# Motor_main.net
KiCad netlist of a schematic drawn in EasyEDA Pro
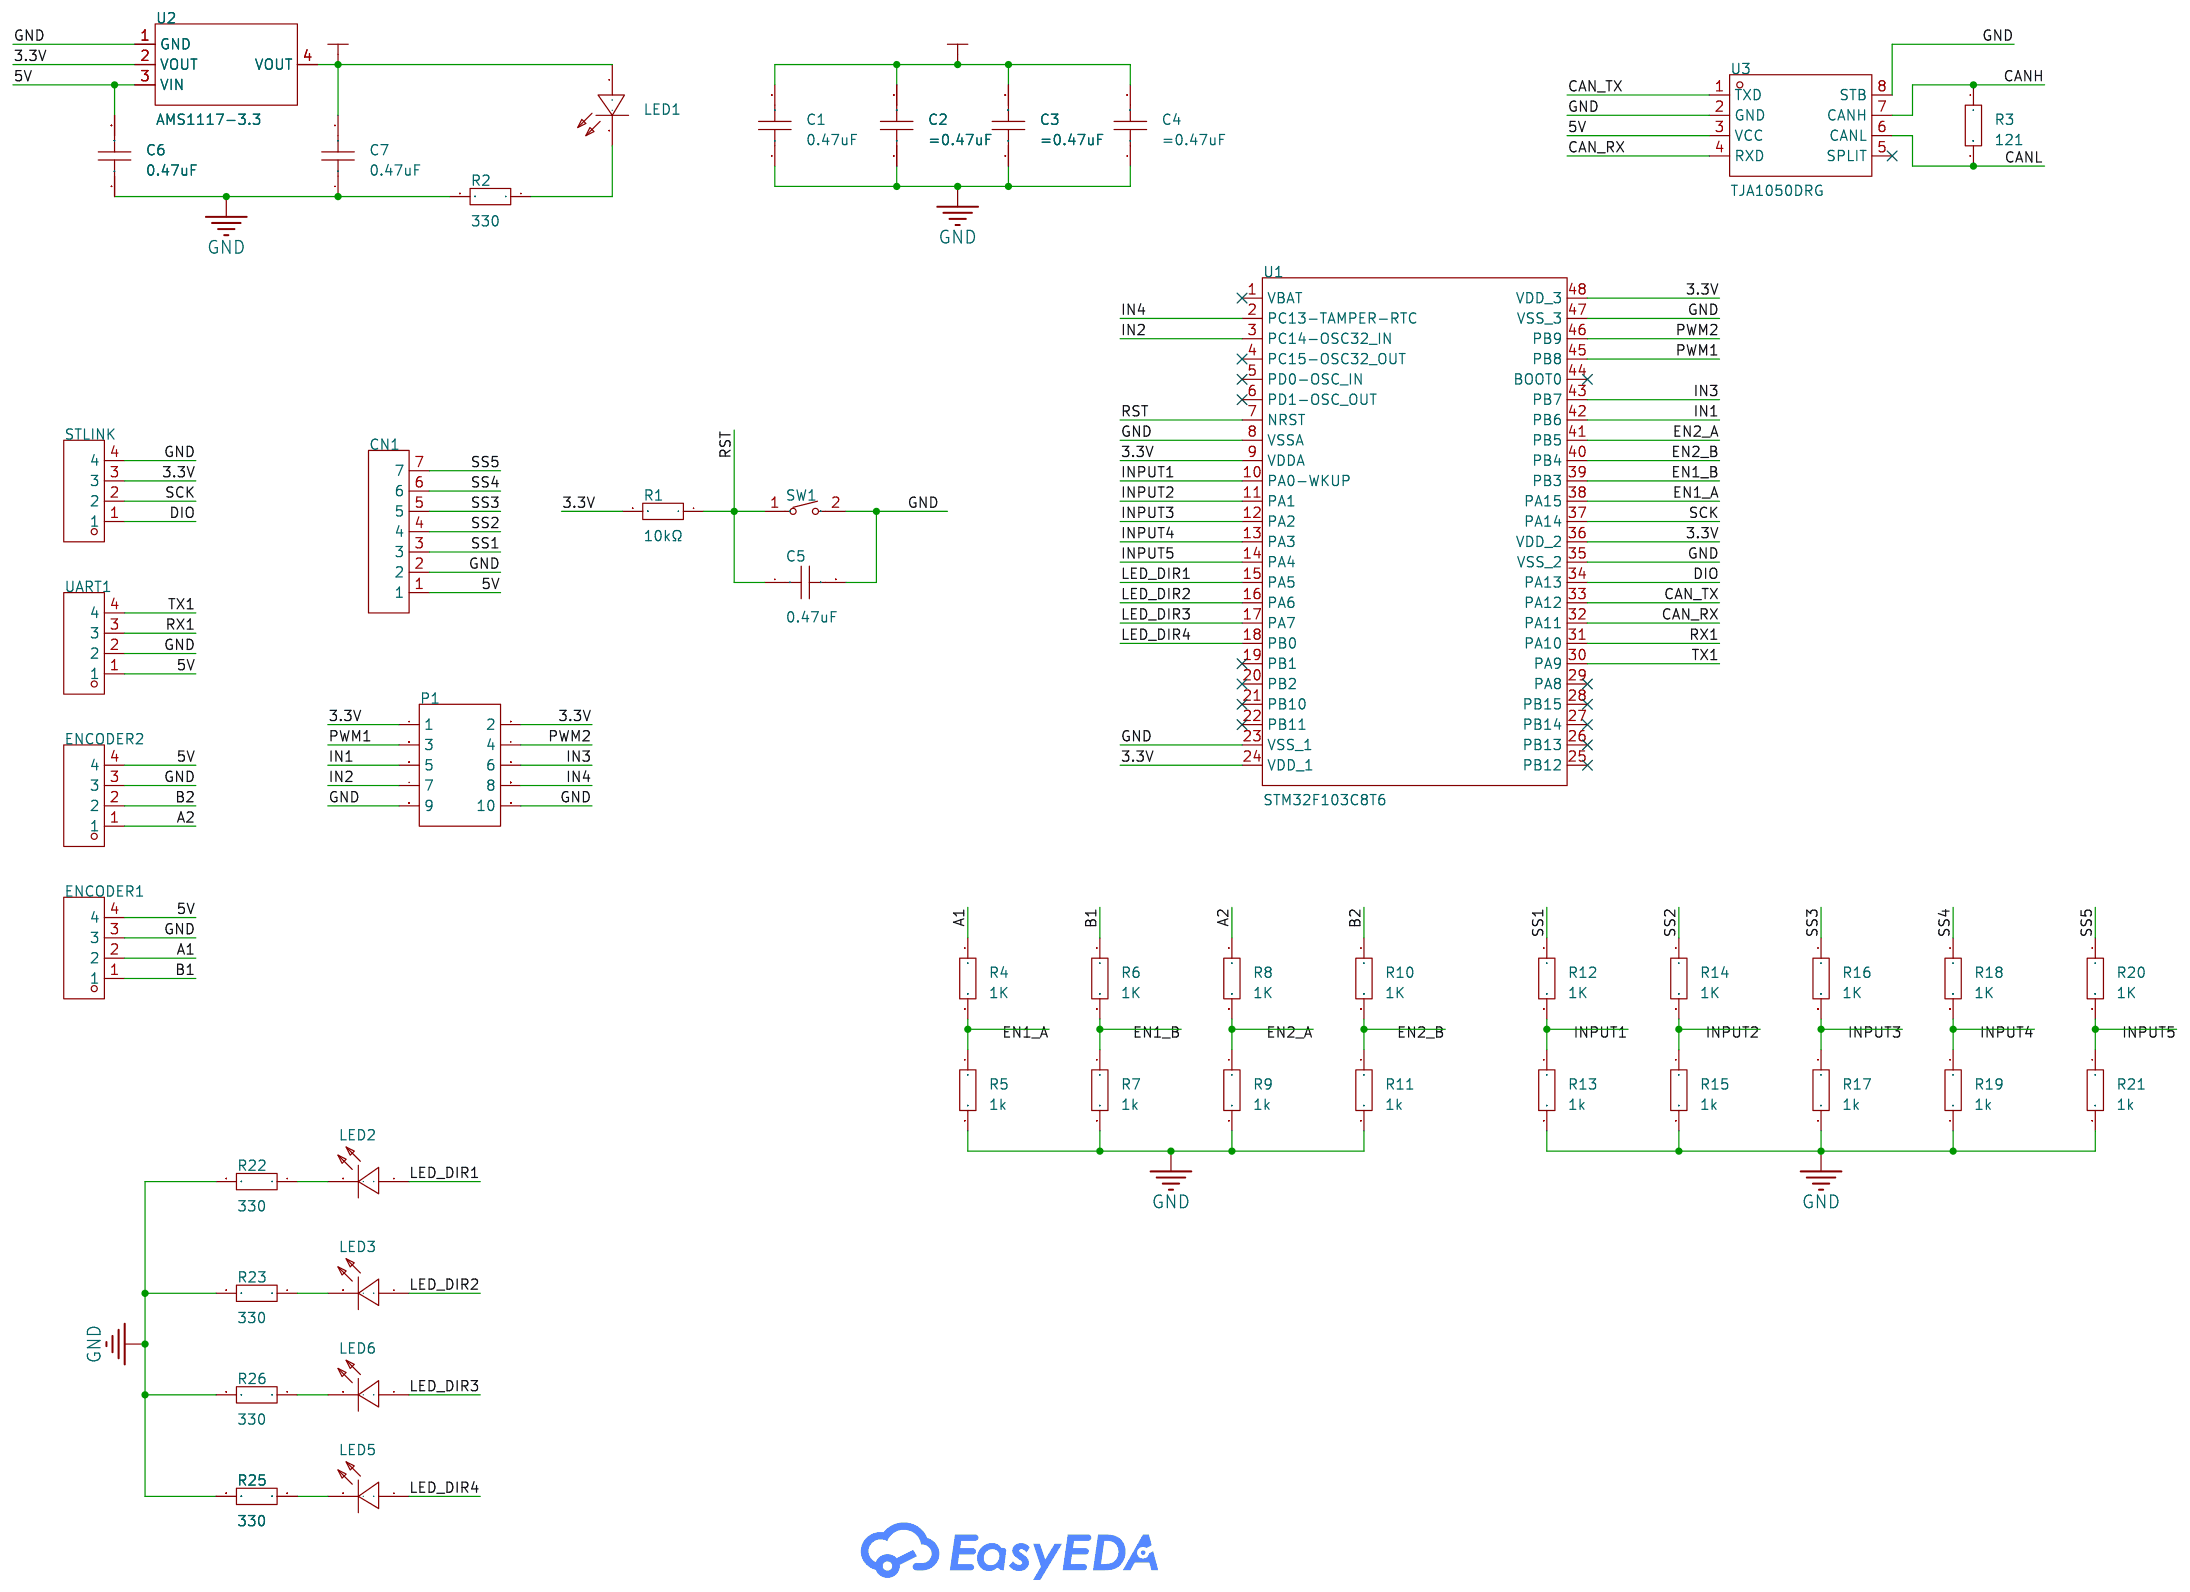
[diagram p0: schematic sheet]

(export (version "E")
  (design (tool "Eeschema 10.0.6"))
  (components
    (comp (ref "C1")
      (value "0.47uF")
      (footprint "easyedapro:C0805")
      (description "Capacitance:100nF Tolerance:±10% Tolerance:±10% Voltage Rating:50V Temperature Coefficient:X7R")
      (fields
        (field (name "Manufacturer Part") "CC0805KRX7R9BB104")
        (field (name "Manufacturer") "YAGEO(国巨)")
      )
      (libsource (lib "easyedapro") (part "CC0805KRX7R9BB104"))
    )
    (comp (ref "C2")
      (value "100nF")
      (footprint "easyedapro:C0805")
      (description "Capacitance:100nF Tolerance:±10% Tolerance:±10% Voltage Rating:50V Temperature Coefficient:X7R")
      (fields
        (field (name "Manufacturer Part") "CC0805KRX7R9BB104")
        (field (name "Manufacturer") "YAGEO(国巨)")
      )
      (libsource (lib "easyedapro") (part "CC0805KRX7R9BB104"))
    )
    (comp (ref "C3")
      (value "100nF")
      (footprint "easyedapro:C0805")
      (description "Capacitance:100nF Tolerance:±10% Tolerance:±10% Voltage Rating:50V Temperature Coefficient:X7R")
      (fields
        (field (name "Manufacturer Part") "CC0805KRX7R9BB104")
        (field (name "Manufacturer") "YAGEO(国巨)")
      )
      (libsource (lib "easyedapro") (part "CC0805KRX7R9BB104"))
    )
    (comp (ref "C4")
      (value "100nF")
      (footprint "easyedapro:C0805")
      (description "Capacitance:100nF Tolerance:±10% Tolerance:±10% Voltage Rating:50V Temperature Coefficient:X7R")
      (fields
        (field (name "Manufacturer Part") "CC0805KRX7R9BB104")
        (field (name "Manufacturer") "YAGEO(国巨)")
      )
      (libsource (lib "easyedapro") (part "CC0805KRX7R9BB104"))
    )
    (comp (ref "C5")
      (value "0.47uF")
      (footprint "easyedapro:C0805")
      (description "Capacitance:100nF Tolerance:±10% Tolerance:±10% Voltage Rating:50V Temperature Coefficient:X7R")
      (fields
        (field (name "Manufacturer Part") "CC0805KRX7R9BB104")
        (field (name "Manufacturer") "YAGEO(国巨)")
      )
      (libsource (lib "easyedapro") (part "CC0805KRX7R9BB104"))
    )
    (comp (ref "C6")
      (value "0.47uF")
      (footprint "easyedapro:C0805")
      (description "Capacitance:100nF Tolerance:±10% Tolerance:±10% Voltage Rating:50V Temperature Coefficient:X7R")
      (fields
        (field (name "Manufacturer Part") "CC0805KRX7R9BB104")
        (field (name "Manufacturer") "YAGEO(国巨)")
      )
      (libsource (lib "easyedapro") (part "CC0805KRX7R9BB104"))
    )
    (comp (ref "C7")
      (value "0.47uF")
      (footprint "easyedapro:C0805")
      (description "Capacitance:100nF Tolerance:±10% Tolerance:±10% Voltage Rating:50V Temperature Coefficient:X7R")
      (fields
        (field (name "Manufacturer Part") "CC0805KRX7R9BB104")
        (field (name "Manufacturer") "YAGEO(国巨)")
      )
      (libsource (lib "easyedapro") (part "CC0805KRX7R9BB104"))
    )
    (comp (ref "CN1")
      (value "WAFER-XH254Z-7AL")
      (footprint "easyedapro:CONN-TH_7P-P2.50_WAFER-XH254Z-7A")
      (fields (field (name "Manufacturer") "HANBO(汉博)"))
      (libsource (lib "easyedapro") (part "WAFER-XH254Z-7AL"))
    )
    (comp (ref "ENCODER1")
      (value "ZX-XH2.54-4PZZ")
      (footprint "easyedapro:CONN-TH_4P-P2.50_4PIN")
      (fields (field (name "Manufacturer") "Megastar(兆星)"))
      (libsource (lib "easyedapro") (part "ZX-XH2.54-4PZZ"))
    )
    (comp (ref "ENCODER2")
      (value "ZX-XH2.54-4PZZ")
      (footprint "easyedapro:CONN-TH_4P-P2.50_4PIN")
      (fields (field (name "Manufacturer") "Megastar(兆星)"))
      (libsource (lib "easyedapro") (part "ZX-XH2.54-4PZZ"))
    )
    (comp (ref "LED1")
      (value "YLED0805R")
      (footprint "easyedapro:LED0805-R-RD_RED")
      (fields (field (name "Manufacturer") "YONGYUTAI(永裕泰)"))
      (libsource (lib "easyedapro") (part "YLED0805R"))
    )
    (comp (ref "LED2")
      (value "YLED0805R")
      (footprint "easyedapro:LED0805-R-RD_RED")
      (fields (field (name "Manufacturer") "YONGYUTAI(永裕泰)"))
      (libsource (lib "easyedapro") (part "YLED0805R"))
    )
    (comp (ref "LED3")
      (value "YLED0805R")
      (footprint "easyedapro:LED0805-R-RD_RED")
      (fields (field (name "Manufacturer") "YONGYUTAI(永裕泰)"))
      (libsource (lib "easyedapro") (part "YLED0805R"))
    )
    (comp (ref "LED5")
      (value "YLED0805R")
      (footprint "easyedapro:LED0805-R-RD_RED")
      (fields (field (name "Manufacturer") "YONGYUTAI(永裕泰)"))
      (libsource (lib "easyedapro") (part "YLED0805R"))
    )
    (comp (ref "LED6")
      (value "YLED0805R")
      (footprint "easyedapro:LED0805-R-RD_RED")
      (fields (field (name "Manufacturer") "YONGYUTAI(永裕泰)"))
      (libsource (lib "easyedapro") (part "YLED0805R"))
    )
    (comp (ref "P1")
      (value "2.54-2*5P简牛")
      (footprint "easyedapro:IDC-TH_10P-P2.54_C5665")
      (fields (field (name "Manufacturer") "BOOMELE(博穆精密)"))
      (libsource (lib "easyedapro") (part "HDR-IDC-2.54-2X5P"))
    )
    (comp (ref "R1")
      (value "10kΩ")
      (footprint "easyedapro:R0805")
      (fields (field (name "Manufacturer Part") "RC0805FR-0710KL") (field (name "Manufacturer") "YAGEO(国巨)"))
      (libsource (lib "easyedapro") (part "RC0805FR-0710KL"))
    )
    (comp (ref "R2")
      (value "10kΩ")
      (footprint "easyedapro:R0805")
      (fields (field (name "Manufacturer Part") "RC0805FR-0710KL") (field (name "Manufacturer") "YAGEO(国巨)"))
      (libsource (lib "easyedapro") (part "RC0805FR-0710KL"))
    )
    (comp (ref "R3")
      (value "10kΩ")
      (footprint "easyedapro:R0805")
      (fields (field (name "Manufacturer Part") "RC0805FR-0710KL") (field (name "Manufacturer") "YAGEO(国巨)"))
      (libsource (lib "easyedapro") (part "RC0805FR-0710KL"))
    )
    (comp (ref "R4")
      (value "1K")
      (footprint "easyedapro:R0805")
      (fields (field (name "Manufacturer Part") "RC0805FR-0710KL") (field (name "Manufacturer") "YAGEO(国巨)"))
      (libsource (lib "easyedapro") (part "RC0805FR-0710KL"))
    )
    (comp (ref "R5")
      (value "1k")
      (footprint "easyedapro:R0805")
      (fields (field (name "Manufacturer Part") "RC0805FR-0710KL") (field (name "Manufacturer") "YAGEO(国巨)"))
      (libsource (lib "easyedapro") (part "RC0805FR-0710KL"))
    )
    (comp (ref "R6")
      (value "1K")
      (footprint "easyedapro:R0805")
      (fields (field (name "Manufacturer Part") "RC0805FR-0710KL") (field (name "Manufacturer") "YAGEO(国巨)"))
      (libsource (lib "easyedapro") (part "RC0805FR-0710KL"))
    )
    (comp (ref "R7")
      (value "1k")
      (footprint "easyedapro:R0805")
      (fields (field (name "Manufacturer Part") "RC0805FR-0710KL") (field (name "Manufacturer") "YAGEO(国巨)"))
      (libsource (lib "easyedapro") (part "RC0805FR-0710KL"))
    )
    (comp (ref "R8")
      (value "1K")
      (footprint "easyedapro:R0805")
      (fields (field (name "Manufacturer Part") "RC0805FR-0710KL") (field (name "Manufacturer") "YAGEO(国巨)"))
      (libsource (lib "easyedapro") (part "RC0805FR-0710KL"))
    )
    (comp (ref "R9")
      (value "1k")
      (footprint "easyedapro:R0805")
      (fields (field (name "Manufacturer Part") "RC0805FR-0710KL") (field (name "Manufacturer") "YAGEO(国巨)"))
      (libsource (lib "easyedapro") (part "RC0805FR-0710KL"))
    )
    (comp (ref "R10")
      (value "1K")
      (footprint "easyedapro:R0805")
      (fields (field (name "Manufacturer Part") "RC0805FR-0710KL") (field (name "Manufacturer") "YAGEO(国巨)"))
      (libsource (lib "easyedapro") (part "RC0805FR-0710KL"))
    )
    (comp (ref "R11")
      (value "1k")
      (footprint "easyedapro:R0805")
      (fields (field (name "Manufacturer Part") "RC0805FR-0710KL") (field (name "Manufacturer") "YAGEO(国巨)"))
      (libsource (lib "easyedapro") (part "RC0805FR-0710KL"))
    )
    (comp (ref "R12")
      (value "1K")
      (footprint "easyedapro:R0805")
      (fields (field (name "Manufacturer Part") "RC0805FR-0710KL") (field (name "Manufacturer") "YAGEO(国巨)"))
      (libsource (lib "easyedapro") (part "RC0805FR-0710KL"))
    )
    (comp (ref "R13")
      (value "1k")
      (footprint "easyedapro:R0805")
      (fields (field (name "Manufacturer Part") "RC0805FR-0710KL") (field (name "Manufacturer") "YAGEO(国巨)"))
      (libsource (lib "easyedapro") (part "RC0805FR-0710KL"))
    )
    (comp (ref "R14")
      (value "1K")
      (footprint "easyedapro:R0805")
      (fields (field (name "Manufacturer Part") "RC0805FR-0710KL") (field (name "Manufacturer") "YAGEO(国巨)"))
      (libsource (lib "easyedapro") (part "RC0805FR-0710KL"))
    )
    (comp (ref "R15")
      (value "1k")
      (footprint "easyedapro:R0805")
      (fields (field (name "Manufacturer Part") "RC0805FR-0710KL") (field (name "Manufacturer") "YAGEO(国巨)"))
      (libsource (lib "easyedapro") (part "RC0805FR-0710KL"))
    )
    (comp (ref "R16")
      (value "1K")
      (footprint "easyedapro:R0805")
      (fields (field (name "Manufacturer Part") "RC0805FR-0710KL") (field (name "Manufacturer") "YAGEO(国巨)"))
      (libsource (lib "easyedapro") (part "RC0805FR-0710KL"))
    )
    (comp (ref "R17")
      (value "1k")
      (footprint "easyedapro:R0805")
      (fields (field (name "Manufacturer Part") "RC0805FR-0710KL") (field (name "Manufacturer") "YAGEO(国巨)"))
      (libsource (lib "easyedapro") (part "RC0805FR-0710KL"))
    )
    (comp (ref "R18")
      (value "1K")
      (footprint "easyedapro:R0805")
      (fields (field (name "Manufacturer Part") "RC0805FR-0710KL") (field (name "Manufacturer") "YAGEO(国巨)"))
      (libsource (lib "easyedapro") (part "RC0805FR-0710KL"))
    )
    (comp (ref "R19")
      (value "1k")
      (footprint "easyedapro:R0805")
      (fields (field (name "Manufacturer Part") "RC0805FR-0710KL") (field (name "Manufacturer") "YAGEO(国巨)"))
      (libsource (lib "easyedapro") (part "RC0805FR-0710KL"))
    )
    (comp (ref "R20")
      (value "1K")
      (footprint "easyedapro:R0805")
      (fields (field (name "Manufacturer Part") "RC0805FR-0710KL") (field (name "Manufacturer") "YAGEO(国巨)"))
      (libsource (lib "easyedapro") (part "RC0805FR-0710KL"))
    )
    (comp (ref "R21")
      (value "1k")
      (footprint "easyedapro:R0805")
      (fields (field (name "Manufacturer Part") "RC0805FR-0710KL") (field (name "Manufacturer") "YAGEO(国巨)"))
      (libsource (lib "easyedapro") (part "RC0805FR-0710KL"))
    )
    (comp (ref "R22")
      (value "10kΩ")
      (footprint "easyedapro:R0805")
      (fields (field (name "Manufacturer Part") "RC0805FR-0710KL") (field (name "Manufacturer") "YAGEO(国巨)"))
      (libsource (lib "easyedapro") (part "RC0805FR-0710KL"))
    )
    (comp (ref "R23")
      (value "10kΩ")
      (footprint "easyedapro:R0805")
      (fields (field (name "Manufacturer Part") "RC0805FR-0710KL") (field (name "Manufacturer") "YAGEO(国巨)"))
      (libsource (lib "easyedapro") (part "RC0805FR-0710KL"))
    )
    (comp (ref "R25")
      (value "10kΩ")
      (footprint "easyedapro:R0805")
      (fields (field (name "Manufacturer Part") "RC0805FR-0710KL") (field (name "Manufacturer") "YAGEO(国巨)"))
      (libsource (lib "easyedapro") (part "RC0805FR-0710KL"))
    )
    (comp (ref "R26")
      (value "10kΩ")
      (footprint "easyedapro:R0805")
      (fields (field (name "Manufacturer Part") "RC0805FR-0710KL") (field (name "Manufacturer") "YAGEO(国巨)"))
      (libsource (lib "easyedapro") (part "RC0805FR-0710KL"))
    )
    (comp (ref "STLINK")
      (value "ZX-XH2.54-4PZZ")
      (footprint "easyedapro:CONN-TH_4P-P2.50_4PIN")
      (fields (field (name "Manufacturer") "Megastar(兆星)"))
      (libsource (lib "easyedapro") (part "ZX-XH2.54-4PZZ"))
    )
    (comp (ref "SW1")
      (value "GT-TC060A-H025-L1S")
      (footprint "easyedapro:SW-SMD_L6.1-W3.5-LS8.0")
      (fields (field (name "Manufacturer") "G-Switch(品赞)"))
      (libsource (lib "easyedapro") (part "GT-TC060A-H025-L1S"))
    )
    (comp (ref "U1")
      (value "STM32F103C8T6")
      (footprint "easyedapro:LQFP-48_L7.0-W7.0-P0.50-LS9.0-BL")
      (fields (field (name "Manufacturer") "ST(意法半导体)"))
      (libsource (lib "easyedapro") (part "STM32F103C8T6"))
    )
    (comp (ref "U2")
      (value "AMS1117-3.3")
      (footprint "easyedapro:SOT-223-3_L6.5-W3.4-P2.30-LS7.0-BR")
      (fields (field (name "Manufacturer") "AMS"))
      (libsource (lib "easyedapro") (part "AMS1117-3.3"))
    )
    (comp (ref "U3")
      (value "TJA1050DRG")
      (footprint "easyedapro:SOP-8_L4.9-W3.9-P1.27-LS6.0-BL")
      (fields (field (name "Manufacturer") "HGC(深圳汉芯)"))
      (libsource (lib "easyedapro") (part "TJA1050DRG"))
    )
    (comp (ref "UART1")
      (value "ZX-XH2.54-4PZZ")
      (footprint "easyedapro:CONN-TH_4P-P2.50_4PIN")
      (fields (field (name "Manufacturer") "Megastar(兆星)"))
      (libsource (lib "easyedapro") (part "ZX-XH2.54-4PZZ"))
    )
  )
  (nets
    (net (code "1") (name "/5V") (class "Default")
      (node (ref "C6") (pin "2") (pinfunction "2_2") (pintype "unspecified"))
      (node (ref "CN1") (pin "1") (pinfunction "1_1") (pintype "unspecified"))
      (node (ref "ENCODER1") (pin "4") (pinfunction "4_4") (pintype "unspecified"))
      (node (ref "ENCODER2") (pin "4") (pinfunction "4_4") (pintype "unspecified"))
      (node (ref "U2") (pin "3") (pinfunction "VIN_3") (pintype "unspecified"))
      (node (ref "U3") (pin "3") (pinfunction "VCC_3") (pintype "unspecified"))
      (node (ref "UART1") (pin "1") (pinfunction "1_1") (pintype "unspecified"))
    )
    (net (code "2") (name "/A1") (class "Default")
      (node (ref "ENCODER1") (pin "2") (pinfunction "2_2") (pintype "unspecified"))
      (node (ref "R4") (pin "1") (pinfunction "1_1") (pintype "input"))
    )
    (net (code "3") (name "/A2") (class "Default")
      (node (ref "ENCODER2") (pin "1") (pinfunction "1_1") (pintype "unspecified"))
      (node (ref "R8") (pin "1") (pinfunction "1_1") (pintype "input"))
    )
    (net (code "4") (name "/B1") (class "Default")
      (node (ref "ENCODER1") (pin "1") (pinfunction "1_1") (pintype "unspecified"))
      (node (ref "R6") (pin "1") (pinfunction "1_1") (pintype "input"))
    )
    (net (code "5") (name "/B2") (class "Default")
      (node (ref "ENCODER2") (pin "2") (pinfunction "2_2") (pintype "unspecified"))
      (node (ref "R10") (pin "1") (pinfunction "1_1") (pintype "input"))
    )
    (net (code "6") (name "/CANH") (class "Default")
      (node (ref "R3") (pin "1") (pinfunction "1_1") (pintype "input"))
      (node (ref "U3") (pin "7") (pinfunction "CANH_7") (pintype "unspecified"))
    )
    (net (code "7") (name "/CANL") (class "Default")
      (node (ref "R3") (pin "2") (pinfunction "2_2") (pintype "input"))
      (node (ref "U3") (pin "6") (pinfunction "CANL_6") (pintype "unspecified"))
    )
    (net (code "8") (name "/CAN_RX") (class "Default")
      (node (ref "U1") (pin "32") (pinfunction "PA11_32") (pintype "unspecified"))
      (node (ref "U3") (pin "4") (pinfunction "RXD_4") (pintype "unspecified"))
    )
    (net (code "9") (name "/CAN_TX") (class "Default")
      (node (ref "U1") (pin "33") (pinfunction "PA12_33") (pintype "unspecified"))
      (node (ref "U3") (pin "1") (pinfunction "TXD_1") (pintype "unspecified"))
    )
    (net (code "10") (name "/DIO") (class "Default")
      (node (ref "STLINK") (pin "1") (pinfunction "1_1") (pintype "unspecified"))
      (node (ref "U1") (pin "34") (pinfunction "PA13_34") (pintype "unspecified"))
    )
    (net (code "11") (name "/EN1_A") (class "Default")
      (node (ref "R4") (pin "2") (pinfunction "2_2") (pintype "input"))
      (node (ref "R5") (pin "1") (pinfunction "1_1") (pintype "input"))
      (node (ref "U1") (pin "38") (pinfunction "PA15_38") (pintype "unspecified"))
    )
    (net (code "12") (name "/EN1_B") (class "Default")
      (node (ref "R6") (pin "2") (pinfunction "2_2") (pintype "input"))
      (node (ref "R7") (pin "1") (pinfunction "1_1") (pintype "input"))
      (node (ref "U1") (pin "39") (pinfunction "PB3_39") (pintype "unspecified"))
    )
    (net (code "13") (name "/EN2_A") (class "Default")
      (node (ref "R8") (pin "2") (pinfunction "2_2") (pintype "input"))
      (node (ref "R9") (pin "1") (pinfunction "1_1") (pintype "input"))
      (node (ref "U1") (pin "41") (pinfunction "PB5_41") (pintype "unspecified"))
    )
    (net (code "14") (name "/EN2_B") (class "Default")
      (node (ref "R10") (pin "2") (pinfunction "2_2") (pintype "input"))
      (node (ref "R11") (pin "1") (pinfunction "1_1") (pintype "input"))
      (node (ref "U1") (pin "40") (pinfunction "PB4_40") (pintype "unspecified"))
    )
    (net (code "15") (name "/IN1") (class "Default")
      (node (ref "P1") (pin "5") (pinfunction "5_5") (pintype "input"))
      (node (ref "U1") (pin "42") (pinfunction "PB6_42") (pintype "unspecified"))
    )
    (net (code "16") (name "/IN2") (class "Default")
      (node (ref "P1") (pin "7") (pinfunction "7_7") (pintype "input"))
      (node (ref "U1") (pin "3") (pinfunction "PC14-OSC32_IN_3") (pintype "unspecified"))
    )
    (net (code "17") (name "/IN3") (class "Default")
      (node (ref "P1") (pin "6") (pinfunction "6_6") (pintype "input"))
      (node (ref "U1") (pin "43") (pinfunction "PB7_43") (pintype "unspecified"))
    )
    (net (code "18") (name "/IN4") (class "Default")
      (node (ref "P1") (pin "8") (pinfunction "8_8") (pintype "input"))
      (node (ref "U1") (pin "2") (pinfunction "PC13-TAMPER-RTC_2") (pintype "unspecified"))
    )
    (net (code "19") (name "/INPUT1") (class "Default")
      (node (ref "R12") (pin "2") (pinfunction "2_2") (pintype "input"))
      (node (ref "R13") (pin "1") (pinfunction "1_1") (pintype "input"))
      (node (ref "U1") (pin "10") (pinfunction "PA0-WKUP_10") (pintype "unspecified"))
    )
    (net (code "20") (name "/INPUT2") (class "Default")
      (node (ref "R14") (pin "2") (pinfunction "2_2") (pintype "input"))
      (node (ref "R15") (pin "1") (pinfunction "1_1") (pintype "input"))
      (node (ref "U1") (pin "11") (pinfunction "PA1_11") (pintype "unspecified"))
    )
    (net (code "21") (name "/INPUT3") (class "Default")
      (node (ref "R16") (pin "2") (pinfunction "2_2") (pintype "input"))
      (node (ref "R17") (pin "1") (pinfunction "1_1") (pintype "input"))
      (node (ref "U1") (pin "12") (pinfunction "PA2_12") (pintype "unspecified"))
    )
    (net (code "22") (name "/INPUT4") (class "Default")
      (node (ref "R18") (pin "2") (pinfunction "2_2") (pintype "input"))
      (node (ref "R19") (pin "1") (pinfunction "1_1") (pintype "input"))
      (node (ref "U1") (pin "13") (pinfunction "PA3_13") (pintype "unspecified"))
    )
    (net (code "23") (name "/INPUT5") (class "Default")
      (node (ref "R20") (pin "2") (pinfunction "2_2") (pintype "input"))
      (node (ref "R21") (pin "1") (pinfunction "1_1") (pintype "input"))
      (node (ref "U1") (pin "14") (pinfunction "PA4_14") (pintype "unspecified"))
    )
    (net (code "24") (name "/LED_DIR1") (class "Default")
      (node (ref "LED2") (pin "1") (pinfunction "+_1") (pintype "unspecified"))
      (node (ref "U1") (pin "15") (pinfunction "PA5_15") (pintype "unspecified"))
    )
    (net (code "25") (name "/LED_DIR2") (class "Default")
      (node (ref "LED3") (pin "1") (pinfunction "+_1") (pintype "unspecified"))
      (node (ref "U1") (pin "16") (pinfunction "PA6_16") (pintype "unspecified"))
    )
    (net (code "26") (name "/LED_DIR3") (class "Default")
      (node (ref "LED6") (pin "1") (pinfunction "+_1") (pintype "unspecified"))
      (node (ref "U1") (pin "17") (pinfunction "PA7_17") (pintype "unspecified"))
    )
    (net (code "27") (name "/LED_DIR4") (class "Default")
      (node (ref "LED5") (pin "1") (pinfunction "+_1") (pintype "unspecified"))
      (node (ref "U1") (pin "18") (pinfunction "PB0_18") (pintype "unspecified"))
    )
    (net (code "28") (name "/PWM1") (class "Default")
      (node (ref "P1") (pin "3") (pinfunction "3_3") (pintype "input"))
      (node (ref "U1") (pin "45") (pinfunction "PB8_45") (pintype "unspecified"))
    )
    (net (code "29") (name "/PWM2") (class "Default")
      (node (ref "P1") (pin "4") (pinfunction "4_4") (pintype "input"))
      (node (ref "U1") (pin "46") (pinfunction "PB9_46") (pintype "unspecified"))
    )
    (net (code "30") (name "/RST") (class "Default")
      (node (ref "C5") (pin "1") (pinfunction "1_1") (pintype "unspecified"))
      (node (ref "R1") (pin "1") (pinfunction "1_1") (pintype "input"))
      (node (ref "SW1") (pin "1") (pinfunction "1_1") (pintype "unspecified"))
      (node (ref "U1") (pin "7") (pinfunction "NRST_7") (pintype "unspecified"))
    )
    (net (code "31") (name "/RX1") (class "Default")
      (node (ref "U1") (pin "31") (pinfunction "PA10_31") (pintype "unspecified"))
      (node (ref "UART1") (pin "3") (pinfunction "3_3") (pintype "unspecified"))
    )
    (net (code "32") (name "/SCK") (class "Default")
      (node (ref "STLINK") (pin "2") (pinfunction "2_2") (pintype "unspecified"))
      (node (ref "U1") (pin "37") (pinfunction "PA14_37") (pintype "unspecified"))
    )
    (net (code "33") (name "/SS1") (class "Default")
      (node (ref "CN1") (pin "3") (pinfunction "3_3") (pintype "unspecified"))
      (node (ref "R12") (pin "1") (pinfunction "1_1") (pintype "input"))
    )
    (net (code "34") (name "/SS2") (class "Default")
      (node (ref "CN1") (pin "4") (pinfunction "4_4") (pintype "unspecified"))
      (node (ref "R14") (pin "1") (pinfunction "1_1") (pintype "input"))
    )
    (net (code "35") (name "/SS3") (class "Default")
      (node (ref "CN1") (pin "5") (pinfunction "5_5") (pintype "unspecified"))
      (node (ref "R16") (pin "1") (pinfunction "1_1") (pintype "input"))
    )
    (net (code "36") (name "/SS4") (class "Default")
      (node (ref "CN1") (pin "6") (pinfunction "6_6") (pintype "unspecified"))
      (node (ref "R18") (pin "1") (pinfunction "1_1") (pintype "input"))
    )
    (net (code "37") (name "/SS5") (class "Default")
      (node (ref "CN1") (pin "7") (pinfunction "7_7") (pintype "unspecified"))
      (node (ref "R20") (pin "1") (pinfunction "1_1") (pintype "input"))
    )
    (net (code "38") (name "/TX1") (class "Default")
      (node (ref "U1") (pin "30") (pinfunction "PA9_30") (pintype "unspecified"))
      (node (ref "UART1") (pin "4") (pinfunction "4_4") (pintype "unspecified"))
    )
    (net (code "39") (name "3.3V") (class "Default")
      (node (ref "C1") (pin "2") (pinfunction "2_2") (pintype "unspecified"))
      (node (ref "C2") (pin "2") (pinfunction "2_2") (pintype "unspecified"))
      (node (ref "C3") (pin "2") (pinfunction "2_2") (pintype "unspecified"))
      (node (ref "C4") (pin "2") (pinfunction "2_2") (pintype "unspecified"))
      (node (ref "C7") (pin "2") (pinfunction "2_2") (pintype "unspecified"))
      (node (ref "LED1") (pin "1") (pinfunction "+_1") (pintype "unspecified"))
      (node (ref "P1") (pin "1") (pinfunction "1_1") (pintype "input"))
      (node (ref "P1") (pin "2") (pinfunction "2_2") (pintype "input"))
      (node (ref "R1") (pin "2") (pinfunction "2_2") (pintype "input"))
      (node (ref "STLINK") (pin "3") (pinfunction "3_3") (pintype "unspecified"))
      (node (ref "U1") (pin "24") (pinfunction "VDD_1_24") (pintype "unspecified"))
      (node (ref "U1") (pin "36") (pinfunction "VDD_2_36") (pintype "unspecified"))
      (node (ref "U1") (pin "48") (pinfunction "VDD_3_48") (pintype "unspecified"))
      (node (ref "U1") (pin "9") (pinfunction "VDDA_9") (pintype "unspecified"))
      (node (ref "U2") (pin "2") (pinfunction "VOUT_2") (pintype "unspecified"))
      (node (ref "U2") (pin "4") (pinfunction "VOUT_4") (pintype "unspecified"))
    )
    (net (code "40") (name "GND") (class "Default")
      (node (ref "C1") (pin "1") (pinfunction "1_1") (pintype "unspecified"))
      (node (ref "C2") (pin "1") (pinfunction "1_1") (pintype "unspecified"))
      (node (ref "C3") (pin "1") (pinfunction "1_1") (pintype "unspecified"))
      (node (ref "C4") (pin "1") (pinfunction "1_1") (pintype "unspecified"))
      (node (ref "C5") (pin "2") (pinfunction "2_2") (pintype "unspecified"))
      (node (ref "C6") (pin "1") (pinfunction "1_1") (pintype "unspecified"))
      (node (ref "C7") (pin "1") (pinfunction "1_1") (pintype "unspecified"))
      (node (ref "CN1") (pin "2") (pinfunction "2_2") (pintype "unspecified"))
      (node (ref "ENCODER1") (pin "3") (pinfunction "3_3") (pintype "unspecified"))
      (node (ref "ENCODER2") (pin "3") (pinfunction "3_3") (pintype "unspecified"))
      (node (ref "P1") (pin "10") (pinfunction "10_10") (pintype "input"))
      (node (ref "P1") (pin "9") (pinfunction "9_9") (pintype "input"))
      (node (ref "R11") (pin "2") (pinfunction "2_2") (pintype "input"))
      (node (ref "R13") (pin "2") (pinfunction "2_2") (pintype "input"))
      (node (ref "R15") (pin "2") (pinfunction "2_2") (pintype "input"))
      (node (ref "R17") (pin "2") (pinfunction "2_2") (pintype "input"))
      (node (ref "R19") (pin "2") (pinfunction "2_2") (pintype "input"))
      (node (ref "R2") (pin "2") (pinfunction "2_2") (pintype "input"))
      (node (ref "R21") (pin "2") (pinfunction "2_2") (pintype "input"))
      (node (ref "R22") (pin "2") (pinfunction "2_2") (pintype "input"))
      (node (ref "R23") (pin "2") (pinfunction "2_2") (pintype "input"))
      (node (ref "R25") (pin "2") (pinfunction "2_2") (pintype "input"))
      (node (ref "R26") (pin "2") (pinfunction "2_2") (pintype "input"))
      (node (ref "R5") (pin "2") (pinfunction "2_2") (pintype "input"))
      (node (ref "R7") (pin "2") (pinfunction "2_2") (pintype "input"))
      (node (ref "R9") (pin "2") (pinfunction "2_2") (pintype "input"))
      (node (ref "STLINK") (pin "4") (pinfunction "4_4") (pintype "unspecified"))
      (node (ref "SW1") (pin "2") (pinfunction "2_2") (pintype "unspecified"))
      (node (ref "U1") (pin "23") (pinfunction "VSS_1_23") (pintype "unspecified"))
      (node (ref "U1") (pin "35") (pinfunction "VSS_2_35") (pintype "unspecified"))
      (node (ref "U1") (pin "47") (pinfunction "VSS_3_47") (pintype "unspecified"))
      (node (ref "U1") (pin "8") (pinfunction "VSSA_8") (pintype "unspecified"))
      (node (ref "U2") (pin "1") (pinfunction "GND_1") (pintype "unspecified"))
      (node (ref "U3") (pin "2") (pinfunction "GND_2") (pintype "unspecified"))
      (node (ref "U3") (pin "8") (pinfunction "STB_8") (pintype "unspecified"))
      (node (ref "UART1") (pin "2") (pinfunction "2_2") (pintype "unspecified"))
    )
    (net (code "41") (name "Net-(LED1--)") (class "Default")
      (node (ref "LED1") (pin "2") (pinfunction "-_2") (pintype "unspecified"))
      (node (ref "R2") (pin "1") (pinfunction "1_1") (pintype "input"))
    )
    (net (code "42") (name "Net-(LED2--)") (class "Default")
      (node (ref "LED2") (pin "2") (pinfunction "-_2") (pintype "unspecified"))
      (node (ref "R22") (pin "1") (pinfunction "1_1") (pintype "input"))
    )
    (net (code "43") (name "Net-(LED3--)") (class "Default")
      (node (ref "LED3") (pin "2") (pinfunction "-_2") (pintype "unspecified"))
      (node (ref "R23") (pin "1") (pinfunction "1_1") (pintype "input"))
    )
    (net (code "44") (name "Net-(LED5--)") (class "Default")
      (node (ref "LED5") (pin "2") (pinfunction "-_2") (pintype "unspecified"))
      (node (ref "R25") (pin "1") (pinfunction "1_1") (pintype "input"))
    )
    (net (code "45") (name "Net-(LED6--)") (class "Default")
      (node (ref "LED6") (pin "2") (pinfunction "-_2") (pintype "unspecified"))
      (node (ref "R26") (pin "1") (pinfunction "1_1") (pintype "input"))
    )
    (net (code "46") (name "unconnected-(U1-BOOT0-Pad44)") (class "Default")
      (node (ref "U1") (pin "44") (pinfunction "BOOT0_44") (pintype "unspecified+no_connect"))
    )
    (net (code "47") (name "unconnected-(U1-PA8-Pad29)") (class "Default")
      (node (ref "U1") (pin "29") (pinfunction "PA8_29") (pintype "unspecified+no_connect"))
    )
    (net (code "48") (name "unconnected-(U1-PB1-Pad19)") (class "Default")
      (node (ref "U1") (pin "19") (pinfunction "PB1_19") (pintype "unspecified+no_connect"))
    )
    (net (code "49") (name "unconnected-(U1-PB2-Pad20)") (class "Default")
      (node (ref "U1") (pin "20") (pinfunction "PB2_20") (pintype "unspecified+no_connect"))
    )
    (net (code "50") (name "unconnected-(U1-PB10-Pad21)") (class "Default")
      (node (ref "U1") (pin "21") (pinfunction "PB10_21") (pintype "unspecified+no_connect"))
    )
    (net (code "51") (name "unconnected-(U1-PB11-Pad22)") (class "Default")
      (node (ref "U1") (pin "22") (pinfunction "PB11_22") (pintype "unspecified+no_connect"))
    )
    (net (code "52") (name "unconnected-(U1-PB12-Pad25)") (class "Default")
      (node (ref "U1") (pin "25") (pinfunction "PB12_25") (pintype "unspecified+no_connect"))
    )
    (net (code "53") (name "unconnected-(U1-PB13-Pad26)") (class "Default")
      (node (ref "U1") (pin "26") (pinfunction "PB13_26") (pintype "unspecified+no_connect"))
    )
    (net (code "54") (name "unconnected-(U1-PB14-Pad27)") (class "Default")
      (node (ref "U1") (pin "27") (pinfunction "PB14_27") (pintype "unspecified+no_connect"))
    )
    (net (code "55") (name "unconnected-(U1-PB15-Pad28)") (class "Default")
      (node (ref "U1") (pin "28") (pinfunction "PB15_28") (pintype "unspecified+no_connect"))
    )
    (net (code "56") (name "unconnected-(U1-PC15-OSC32_OUT-Pad4)") (class "Default")
      (node (ref "U1") (pin "4") (pinfunction "PC15-OSC32_OUT_4") (pintype "unspecified+no_connect"))
    )
    (net (code "57") (name "unconnected-(U1-PD0-OSC_IN-Pad5)") (class "Default")
      (node (ref "U1") (pin "5") (pinfunction "PD0-OSC_IN_5") (pintype "unspecified+no_connect"))
    )
    (net (code "58") (name "unconnected-(U1-PD1-OSC_OUT-Pad6)") (class "Default")
      (node (ref "U1") (pin "6") (pinfunction "PD1-OSC_OUT_6") (pintype "unspecified+no_connect"))
    )
    (net (code "59") (name "unconnected-(U1-VBAT-Pad1)") (class "Default")
      (node (ref "U1") (pin "1") (pinfunction "VBAT_1") (pintype "unspecified+no_connect"))
    )
    (net (code "60") (name "unconnected-(U3-SPLIT-Pad5)") (class "Default")
      (node (ref "U3") (pin "5") (pinfunction "SPLIT_5") (pintype "unspecified+no_connect"))
    )
  )
)
